# PC_CurveTracer.net
KiCad netlist of a schematic drawn in EAGLE
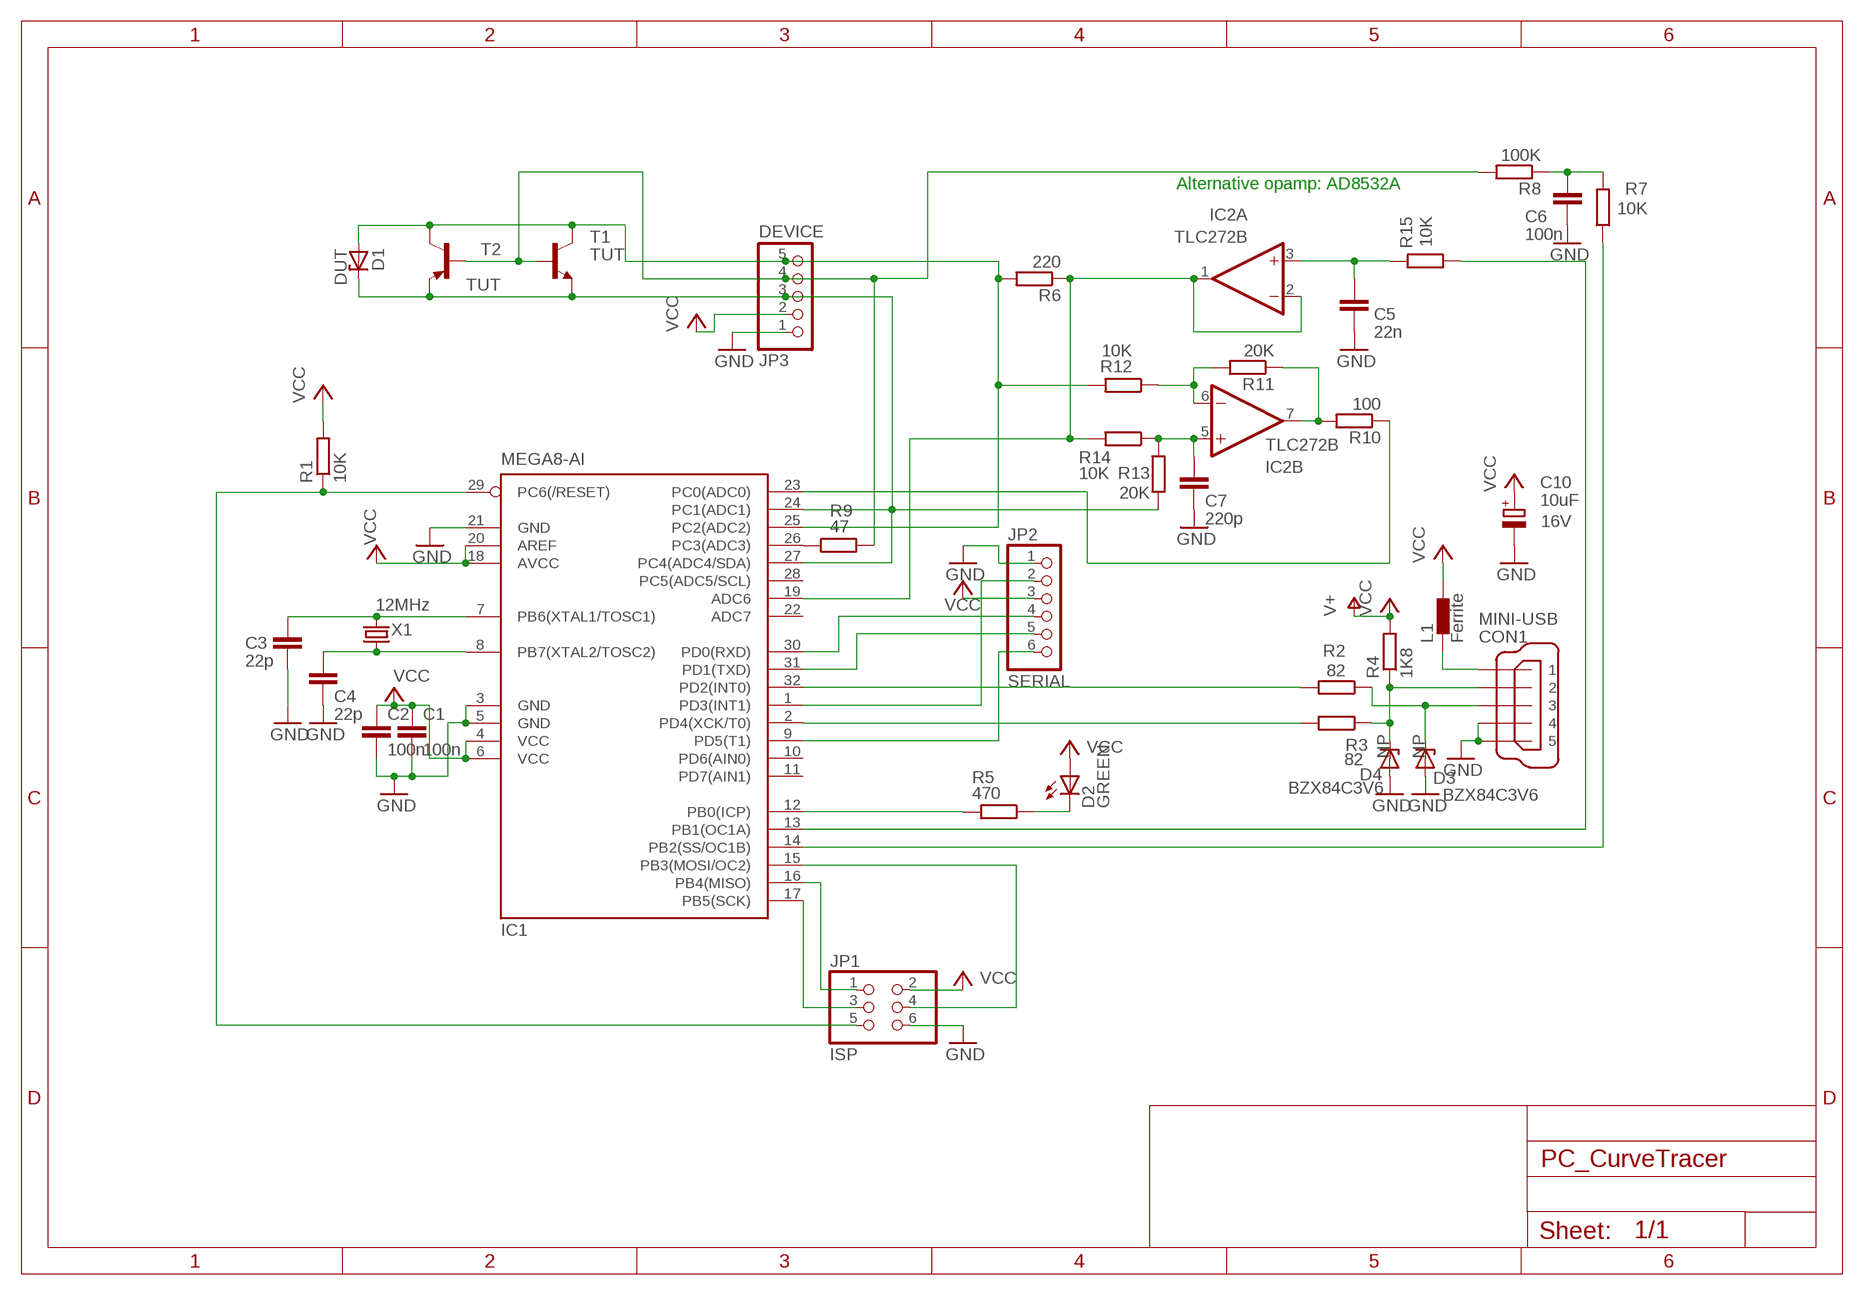
[diagram p0: schematic, sheet 1]

(export (version "E")
  (design (tool "Eeschema 10.0.6"))
  (components
    (comp (ref "C1")
      (value "100n")
      (footprint "eagle-import:C1206")
      (libsource (lib "eagle-import") (part "C-EUC1206"))
    )
    (comp (ref "C2")
      (value "100n")
      (footprint "eagle-import:C1206")
      (libsource (lib "eagle-import") (part "C-EUC1206"))
    )
    (comp (ref "C3")
      (value "22p")
      (footprint "eagle-import:C0603")
      (libsource (lib "eagle-import") (part "C-EUC0603"))
    )
    (comp (ref "C4")
      (value "22p")
      (footprint "eagle-import:C0603")
      (libsource (lib "eagle-import") (part "C-EUC0603"))
    )
    (comp (ref "C5")
      (value "22n")
      (footprint "eagle-import:C1206")
      (libsource (lib "eagle-import") (part "C-EUC1206"))
    )
    (comp (ref "C6")
      (value "100n")
      (footprint "eagle-import:C1206")
      (libsource (lib "eagle-import") (part "C-EUC1206"))
    )
    (comp (ref "C7")
      (value "220p")
      (footprint "eagle-import:C1206")
      (libsource (lib "eagle-import") (part "C-EUC1206"))
    )
    (comp (ref "C10")
      (value "10uF")
      (footprint "eagle-import:SMC_C")
      (fields (field (name "VOLTAGE") "16V"))
      (libsource (lib "eagle-import") (part "CPOL-EUSMCC"))
    )
    (comp (ref "CON1")
      (value "MINI-USB")
      (footprint "eagle-import:32005-400")
      (libsource (lib "eagle-import") (part "MINI-USB_SHIELD5P4-32005-400"))
    )
    (comp (ref "D1")
      (value "DUT")
      (footprint "eagle-import:SOD80C")
      (libsource (lib "eagle-import") (part "ZENER-DIODESOD80C"))
    )
    (comp (ref "D2")
      (value "GREEN")
      (footprint "eagle-import:SML0805")
      (libsource (lib "eagle-import") (part "LEDSML0805"))
    )
    (comp (ref "D3")
      (value "BZX84C3V6")
      (footprint "eagle-import:TO236")
      (fields (field (name "NP") "NP"))
      (libsource (lib "eagle-import") (part "BZX84CSMD"))
    )
    (comp (ref "D4")
      (value "BZX84C3V6")
      (footprint "eagle-import:TO236")
      (fields (field (name "NP") "NP"))
      (libsource (lib "eagle-import") (part "BZX84CSMD"))
    )
    (comp (ref "IC1")
      (value "MEGA8-AI")
      (footprint "eagle-import:TQFP32-08")
      (fields (field (name "MPN") "ATMEGA8-16AU"))
      (libsource (lib "eagle-import") (part "MEGA8-AI"))
    )
    (comp (ref "IC2")
      (value "TLC272B")
      (footprint "eagle-import:SO08")
      (libsource (lib "eagle-import") (part "LM358D"))
    )
    (comp (ref "JP1")
      (value "ISP")
      (footprint "eagle-import:2X03")
      (libsource (lib "eagle-import") (part "PINHD-2X3"))
    )
    (comp (ref "JP2")
      (value "SERIAL")
      (footprint "eagle-import:1X06")
      (libsource (lib "eagle-import") (part "PINHD-1X6"))
    )
    (comp (ref "JP3")
      (value "DEVICE")
      (footprint "eagle-import:1X05")
      (libsource (lib "eagle-import") (part "PINHD-1X5"))
    )
    (comp (ref "L1")
      (value "Ferrite")
      (footprint "eagle-import:0402")
      (libsource (lib "eagle-import") (part "BLM15HG601SN1"))
    )
    (comp (ref "R1")
      (value "10K")
      (footprint "eagle-import:R1206")
      (libsource (lib "eagle-import") (part "R-EU_R1206"))
    )
    (comp (ref "R2")
      (value "82")
      (footprint "eagle-import:R1206")
      (libsource (lib "eagle-import") (part "R-EU_R1206"))
    )
    (comp (ref "R3")
      (value "82")
      (footprint "eagle-import:R1206")
      (libsource (lib "eagle-import") (part "R-EU_R1206"))
    )
    (comp (ref "R4")
      (value "1K8")
      (footprint "eagle-import:R1206")
      (libsource (lib "eagle-import") (part "R-EU_R1206"))
    )
    (comp (ref "R5")
      (value "470")
      (footprint "eagle-import:R1206")
      (libsource (lib "eagle-import") (part "R-EU_R1206"))
    )
    (comp (ref "R6")
      (value "220")
      (footprint "eagle-import:R1206")
      (libsource (lib "eagle-import") (part "R-EU_R1206"))
    )
    (comp (ref "R7")
      (value "10K")
      (footprint "eagle-import:R1206")
      (libsource (lib "eagle-import") (part "R-EU_R1206"))
    )
    (comp (ref "R8")
      (value "100K")
      (footprint "eagle-import:R1206")
      (libsource (lib "eagle-import") (part "R-EU_R1206"))
    )
    (comp (ref "R9")
      (value "47")
      (footprint "eagle-import:R1206")
      (libsource (lib "eagle-import") (part "R-EU_R1206"))
    )
    (comp (ref "R10")
      (value "100")
      (footprint "eagle-import:R1206")
      (libsource (lib "eagle-import") (part "R-EU_R1206"))
    )
    (comp (ref "R11")
      (value "20K")
      (footprint "eagle-import:R1206")
      (libsource (lib "eagle-import") (part "R-EU_R1206"))
    )
    (comp (ref "R12")
      (value "10K")
      (footprint "eagle-import:R1206")
      (libsource (lib "eagle-import") (part "R-EU_R1206"))
    )
    (comp (ref "R13")
      (value "20K")
      (footprint "eagle-import:R1206")
      (libsource (lib "eagle-import") (part "R-EU_R1206"))
    )
    (comp (ref "R14")
      (value "10K")
      (footprint "eagle-import:R1206")
      (libsource (lib "eagle-import") (part "R-EU_R1206"))
    )
    (comp (ref "R15")
      (value "10K")
      (footprint "eagle-import:R1206")
      (libsource (lib "eagle-import") (part "R-EU_R1206"))
    )
    (comp (ref "T1")
      (value "TUT")
      (footprint "eagle-import:SOT23")
      (libsource (lib "eagle-import") (part "BC846"))
    )
    (comp (ref "T2")
      (value "TUT")
      (footprint "eagle-import:SOT89-ECB")
      (libsource (lib "eagle-import") (part "-PNP-SOT89-ECB"))
    )
    (comp (ref "X1")
      (value "12MHz")
      (footprint "eagle-import:HC49_S")
      (libsource (lib "eagle-import") (part "CRYSTALHC49S"))
    )
  )
  (nets
    (net (code "1") (name "GND") (class "Default")
      (node (ref "C1") (pin "2") (pinfunction "2_2") (pintype "passive"))
      (node (ref "C10") (pin "-") (pinfunction "-_-") (pintype "passive"))
      (node (ref "C2") (pin "2") (pinfunction "2_2") (pintype "passive"))
      (node (ref "C3") (pin "2") (pinfunction "2_2") (pintype "passive"))
      (node (ref "C4") (pin "2") (pinfunction "2_2") (pintype "passive"))
      (node (ref "C5") (pin "2") (pinfunction "2_2") (pintype "passive"))
      (node (ref "C6") (pin "2") (pinfunction "2_2") (pintype "passive"))
      (node (ref "C7") (pin "2") (pinfunction "2_2") (pintype "passive"))
      (node (ref "CON1") (pin "4") (pinfunction "4_4") (pintype "passive"))
      (node (ref "CON1") (pin "5") (pinfunction "5_5") (pintype "passive"))
      (node (ref "D3") (pin "A") (pinfunction "A_A") (pintype "passive"))
      (node (ref "D4") (pin "A") (pinfunction "A_A") (pintype "passive"))
      (node (ref "IC1") (pin "21") (pinfunction "GND_21") (pintype "power_in"))
      (node (ref "IC1") (pin "3") (pinfunction "GND_3") (pintype "power_in"))
      (node (ref "IC1") (pin "5") (pinfunction "GND_5") (pintype "power_in"))
      (node (ref "JP1") (pin "6") (pinfunction "6_6") (pintype "passive"))
      (node (ref "JP2") (pin "1") (pinfunction "1_1") (pintype "passive"))
      (node (ref "JP3") (pin "1") (pinfunction "1_1") (pintype "passive"))
    )
    (net (code "2") (name "Net-(C6-Pad1)") (class "Default")
      (node (ref "C6") (pin "1") (pinfunction "1_1") (pintype "passive"))
      (node (ref "R7") (pin "2") (pinfunction "2_2") (pintype "passive"))
      (node (ref "R8") (pin "1") (pinfunction "1_1") (pintype "passive"))
    )
    (net (code "3") (name "Net-(CON1-Pad1)") (class "Default")
      (node (ref "CON1") (pin "1") (pinfunction "1_1") (pintype "passive"))
      (node (ref "L1") (pin "1") (pinfunction "1_1") (pintype "passive"))
    )
    (net (code "4") (name "Net-(CON1-Pad2)") (class "Default")
      (node (ref "CON1") (pin "2") (pinfunction "2_2") (pintype "passive"))
      (node (ref "D4") (pin "C") (pinfunction "C_C") (pintype "passive"))
      (node (ref "R3") (pin "1") (pinfunction "1_1") (pintype "passive"))
      (node (ref "R4") (pin "1") (pinfunction "1_1") (pintype "passive"))
    )
    (net (code "5") (name "Net-(CON1-Pad3)") (class "Default")
      (node (ref "CON1") (pin "3") (pinfunction "3_3") (pintype "passive"))
      (node (ref "D3") (pin "C") (pinfunction "C_C") (pintype "passive"))
      (node (ref "R2") (pin "1") (pinfunction "1_1") (pintype "passive"))
    )
    (net (code "6") (name "Net-(D2-PadC)") (class "Default")
      (node (ref "D2") (pin "C") (pinfunction "C_C") (pintype "passive"))
      (node (ref "R5") (pin "1") (pinfunction "1_1") (pintype "passive"))
    )
    (net (code "7") (name "Net-(IC1-ADC6)") (class "Default")
      (node (ref "IC1") (pin "19") (pinfunction "ADC6_19") (pintype "bidirectional"))
      (node (ref "IC2") (pin "1") (pinfunction "OUT_1") (pintype "output"))
      (node (ref "IC2") (pin "2") (pinfunction "-IN_2") (pintype "input"))
      (node (ref "R14") (pin "2") (pinfunction "2_2") (pintype "passive"))
      (node (ref "R6") (pin "1") (pinfunction "1_1") (pintype "passive"))
    )
    (net (code "8") (name "Net-(IC1-PB0(ICP))") (class "Default")
      (node (ref "IC1") (pin "12") (pinfunction "PB0(ICP)_12") (pintype "bidirectional"))
      (node (ref "R5") (pin "2") (pinfunction "2_2") (pintype "passive"))
    )
    (net (code "9") (name "Net-(IC1-PB1(OC1A))") (class "Default")
      (node (ref "IC1") (pin "13") (pinfunction "PB1(OC1A)_13") (pintype "bidirectional"))
      (node (ref "R15") (pin "1") (pinfunction "1_1") (pintype "passive"))
    )
    (net (code "10") (name "Net-(IC1-PB2(SS{slash}OC1B))") (class "Default")
      (node (ref "IC1") (pin "14") (pinfunction "PB2(SS/OC1B)_14") (pintype "bidirectional"))
      (node (ref "R7") (pin "1") (pinfunction "1_1") (pintype "passive"))
    )
    (net (code "11") (name "Net-(IC1-PB3(MOSI{slash}OC2))") (class "Default")
      (node (ref "IC1") (pin "15") (pinfunction "PB3(MOSI/OC2)_15") (pintype "bidirectional"))
      (node (ref "JP1") (pin "4") (pinfunction "4_4") (pintype "passive"))
    )
    (net (code "12") (name "Net-(IC1-PB4(MISO))") (class "Default")
      (node (ref "IC1") (pin "16") (pinfunction "PB4(MISO)_16") (pintype "bidirectional"))
      (node (ref "JP1") (pin "1") (pinfunction "1_1") (pintype "passive"))
    )
    (net (code "13") (name "Net-(IC1-PB5(SCK))") (class "Default")
      (node (ref "IC1") (pin "17") (pinfunction "PB5(SCK)_17") (pintype "bidirectional"))
      (node (ref "JP1") (pin "3") (pinfunction "3_3") (pintype "passive"))
    )
    (net (code "14") (name "Net-(IC1-PB6(XTAL1{slash}TOSC1))") (class "Default")
      (node (ref "C3") (pin "1") (pinfunction "1_1") (pintype "passive"))
      (node (ref "IC1") (pin "7") (pinfunction "PB6(XTAL1/TOSC1)_7") (pintype "bidirectional"))
      (node (ref "X1") (pin "2") (pinfunction "2_2") (pintype "passive"))
    )
    (net (code "15") (name "Net-(IC1-PB7(XTAL2{slash}TOSC2))") (class "Default")
      (node (ref "C4") (pin "1") (pinfunction "1_1") (pintype "passive"))
      (node (ref "IC1") (pin "8") (pinfunction "PB7(XTAL2/TOSC2)_8") (pintype "bidirectional"))
      (node (ref "X1") (pin "1") (pinfunction "1_1") (pintype "passive"))
    )
    (net (code "16") (name "Net-(IC1-PC0(ADC0))") (class "Default")
      (node (ref "IC1") (pin "23") (pinfunction "PC0(ADC0)_23") (pintype "bidirectional"))
      (node (ref "R10") (pin "1") (pinfunction "1_1") (pintype "passive"))
    )
    (net (code "17") (name "Net-(IC1-PC1(ADC1))") (class "Default")
      (node (ref "D1") (pin "C") (pinfunction "C_C") (pintype "passive"))
      (node (ref "IC1") (pin "24") (pinfunction "PC1(ADC1)_24") (pintype "bidirectional"))
      (node (ref "IC1") (pin "27") (pinfunction "PC4(ADC4/SDA)_27") (pintype "bidirectional"))
      (node (ref "JP3") (pin "3") (pinfunction "3_3") (pintype "passive"))
      (node (ref "R13") (pin "1") (pinfunction "1_1") (pintype "passive"))
      (node (ref "T1") (pin "2") (pinfunction "E_2") (pintype "passive"))
      (node (ref "T2") (pin "E") (pinfunction "E_E") (pintype "passive"))
    )
    (net (code "18") (name "Net-(IC1-PC2(ADC2))") (class "Default")
      (node (ref "D1") (pin "A") (pinfunction "A_A") (pintype "passive"))
      (node (ref "IC1") (pin "25") (pinfunction "PC2(ADC2)_25") (pintype "bidirectional"))
      (node (ref "JP3") (pin "5") (pinfunction "5_5") (pintype "passive"))
      (node (ref "R12") (pin "2") (pinfunction "2_2") (pintype "passive"))
      (node (ref "R6") (pin "2") (pinfunction "2_2") (pintype "passive"))
      (node (ref "T1") (pin "3") (pinfunction "C_3") (pintype "passive"))
      (node (ref "T2") (pin "C") (pinfunction "C_C") (pintype "passive"))
    )
    (net (code "19") (name "Net-(IC1-PC3(ADC3))") (class "Default")
      (node (ref "IC1") (pin "26") (pinfunction "PC3(ADC3)_26") (pintype "bidirectional"))
      (node (ref "R9") (pin "1") (pinfunction "1_1") (pintype "passive"))
    )
    (net (code "20") (name "Net-(IC1-PC6({slash}RESET))") (class "Default")
      (node (ref "IC1") (pin "29") (pinfunction "PC6(/RESET)_29") (pintype "bidirectional"))
      (node (ref "JP1") (pin "5") (pinfunction "5_5") (pintype "passive"))
      (node (ref "R1") (pin "1") (pinfunction "1_1") (pintype "passive"))
    )
    (net (code "21") (name "Net-(IC1-PD0(RXD))") (class "Default")
      (node (ref "IC1") (pin "30") (pinfunction "PD0(RXD)_30") (pintype "bidirectional"))
      (node (ref "JP2") (pin "4") (pinfunction "4_4") (pintype "passive"))
    )
    (net (code "22") (name "Net-(IC1-PD1(TXD))") (class "Default")
      (node (ref "IC1") (pin "31") (pinfunction "PD1(TXD)_31") (pintype "bidirectional"))
      (node (ref "JP2") (pin "5") (pinfunction "5_5") (pintype "passive"))
    )
    (net (code "23") (name "Net-(IC1-PD2(INT0))") (class "Default")
      (node (ref "IC1") (pin "32") (pinfunction "PD2(INT0)_32") (pintype "bidirectional"))
      (node (ref "R2") (pin "2") (pinfunction "2_2") (pintype "passive"))
    )
    (net (code "24") (name "Net-(IC1-PD3(INT1))") (class "Default")
      (node (ref "IC1") (pin "1") (pinfunction "PD3(INT1)_1") (pintype "bidirectional"))
      (node (ref "JP2") (pin "2") (pinfunction "2_2") (pintype "passive"))
    )
    (net (code "25") (name "Net-(IC1-PD4(XCK{slash}T0))") (class "Default")
      (node (ref "IC1") (pin "2") (pinfunction "PD4(XCK/T0)_2") (pintype "bidirectional"))
      (node (ref "R3") (pin "2") (pinfunction "2_2") (pintype "passive"))
    )
    (net (code "26") (name "Net-(IC1-PD5(T1))") (class "Default")
      (node (ref "IC1") (pin "9") (pinfunction "PD5(T1)_9") (pintype "bidirectional"))
      (node (ref "JP2") (pin "6") (pinfunction "6_6") (pintype "passive"))
    )
    (net (code "27") (name "Net-(IC2A-+IN)") (class "Default")
      (node (ref "C5") (pin "1") (pinfunction "1_1") (pintype "passive"))
      (node (ref "IC2") (pin "3") (pinfunction "+IN_3") (pintype "input"))
      (node (ref "R15") (pin "2") (pinfunction "2_2") (pintype "passive"))
    )
    (net (code "28") (name "Net-(IC2B-+IN)") (class "Default")
      (node (ref "C7") (pin "1") (pinfunction "1_1") (pintype "passive"))
      (node (ref "IC2") (pin "5") (pinfunction "+IN_5") (pintype "input"))
      (node (ref "R13") (pin "2") (pinfunction "2_2") (pintype "passive"))
      (node (ref "R14") (pin "1") (pinfunction "1_1") (pintype "passive"))
    )
    (net (code "29") (name "Net-(IC2B--IN)") (class "Default")
      (node (ref "IC2") (pin "6") (pinfunction "-IN_6") (pintype "input"))
      (node (ref "R11") (pin "2") (pinfunction "2_2") (pintype "passive"))
      (node (ref "R12") (pin "1") (pinfunction "1_1") (pintype "passive"))
    )
    (net (code "30") (name "Net-(IC2B-OUT)") (class "Default")
      (node (ref "IC2") (pin "7") (pinfunction "OUT_7") (pintype "output"))
      (node (ref "R10") (pin "2") (pinfunction "2_2") (pintype "passive"))
      (node (ref "R11") (pin "1") (pinfunction "1_1") (pintype "passive"))
    )
    (net (code "31") (name "Net-(T1-B)") (class "Default")
      (node (ref "JP3") (pin "4") (pinfunction "4_4") (pintype "passive"))
      (node (ref "R8") (pin "2") (pinfunction "2_2") (pintype "passive"))
      (node (ref "R9") (pin "2") (pinfunction "2_2") (pintype "passive"))
      (node (ref "T1") (pin "1") (pinfunction "B_1") (pintype "passive"))
      (node (ref "T2") (pin "B") (pinfunction "B_B") (pintype "passive"))
    )
    (net (code "32") (name "V+") (class "Default")
      (node (ref "C1") (pin "1") (pinfunction "1_1") (pintype "passive"))
      (node (ref "C10") (pin "+") (pinfunction "+_+") (pintype "passive"))
      (node (ref "C2") (pin "1") (pinfunction "1_1") (pintype "passive"))
      (node (ref "D2") (pin "A") (pinfunction "A_A") (pintype "passive"))
      (node (ref "IC1") (pin "18") (pinfunction "AVCC_18") (pintype "power_in"))
      (node (ref "IC1") (pin "20") (pinfunction "AREF_20") (pintype "passive"))
      (node (ref "IC1") (pin "4") (pinfunction "VCC_4") (pintype "power_in"))
      (node (ref "IC1") (pin "6") (pinfunction "VCC_6") (pintype "power_in"))
      (node (ref "JP1") (pin "2") (pinfunction "2_2") (pintype "passive"))
      (node (ref "JP2") (pin "3") (pinfunction "3_3") (pintype "passive"))
      (node (ref "JP3") (pin "2") (pinfunction "2_2") (pintype "passive"))
      (node (ref "L1") (pin "2") (pinfunction "2_2") (pintype "passive"))
      (node (ref "R1") (pin "2") (pinfunction "2_2") (pintype "passive"))
      (node (ref "R4") (pin "2") (pinfunction "2_2") (pintype "passive"))
    )
    (net (code "33") (name "unconnected-(IC1-ADC7-Pad22)") (class "Default")
      (node (ref "IC1") (pin "22") (pinfunction "ADC7_22") (pintype "bidirectional"))
    )
    (net (code "34") (name "unconnected-(IC1-PC5(ADC5{slash}SCL)-Pad28)") (class "Default")
      (node (ref "IC1") (pin "28") (pinfunction "PC5(ADC5/SCL)_28") (pintype "bidirectional"))
    )
    (net (code "35") (name "unconnected-(IC1-PD6(AIN0)-Pad10)") (class "Default")
      (node (ref "IC1") (pin "10") (pinfunction "PD6(AIN0)_10") (pintype "bidirectional"))
    )
    (net (code "36") (name "unconnected-(IC1-PD7(AIN1)-Pad11)") (class "Default")
      (node (ref "IC1") (pin "11") (pinfunction "PD7(AIN1)_11") (pintype "bidirectional"))
    )
  )
)
